# Grove_-_CO2_Temperature_Humidity_Sensor_.net
KiCad netlist of a schematic drawn in EAGLE
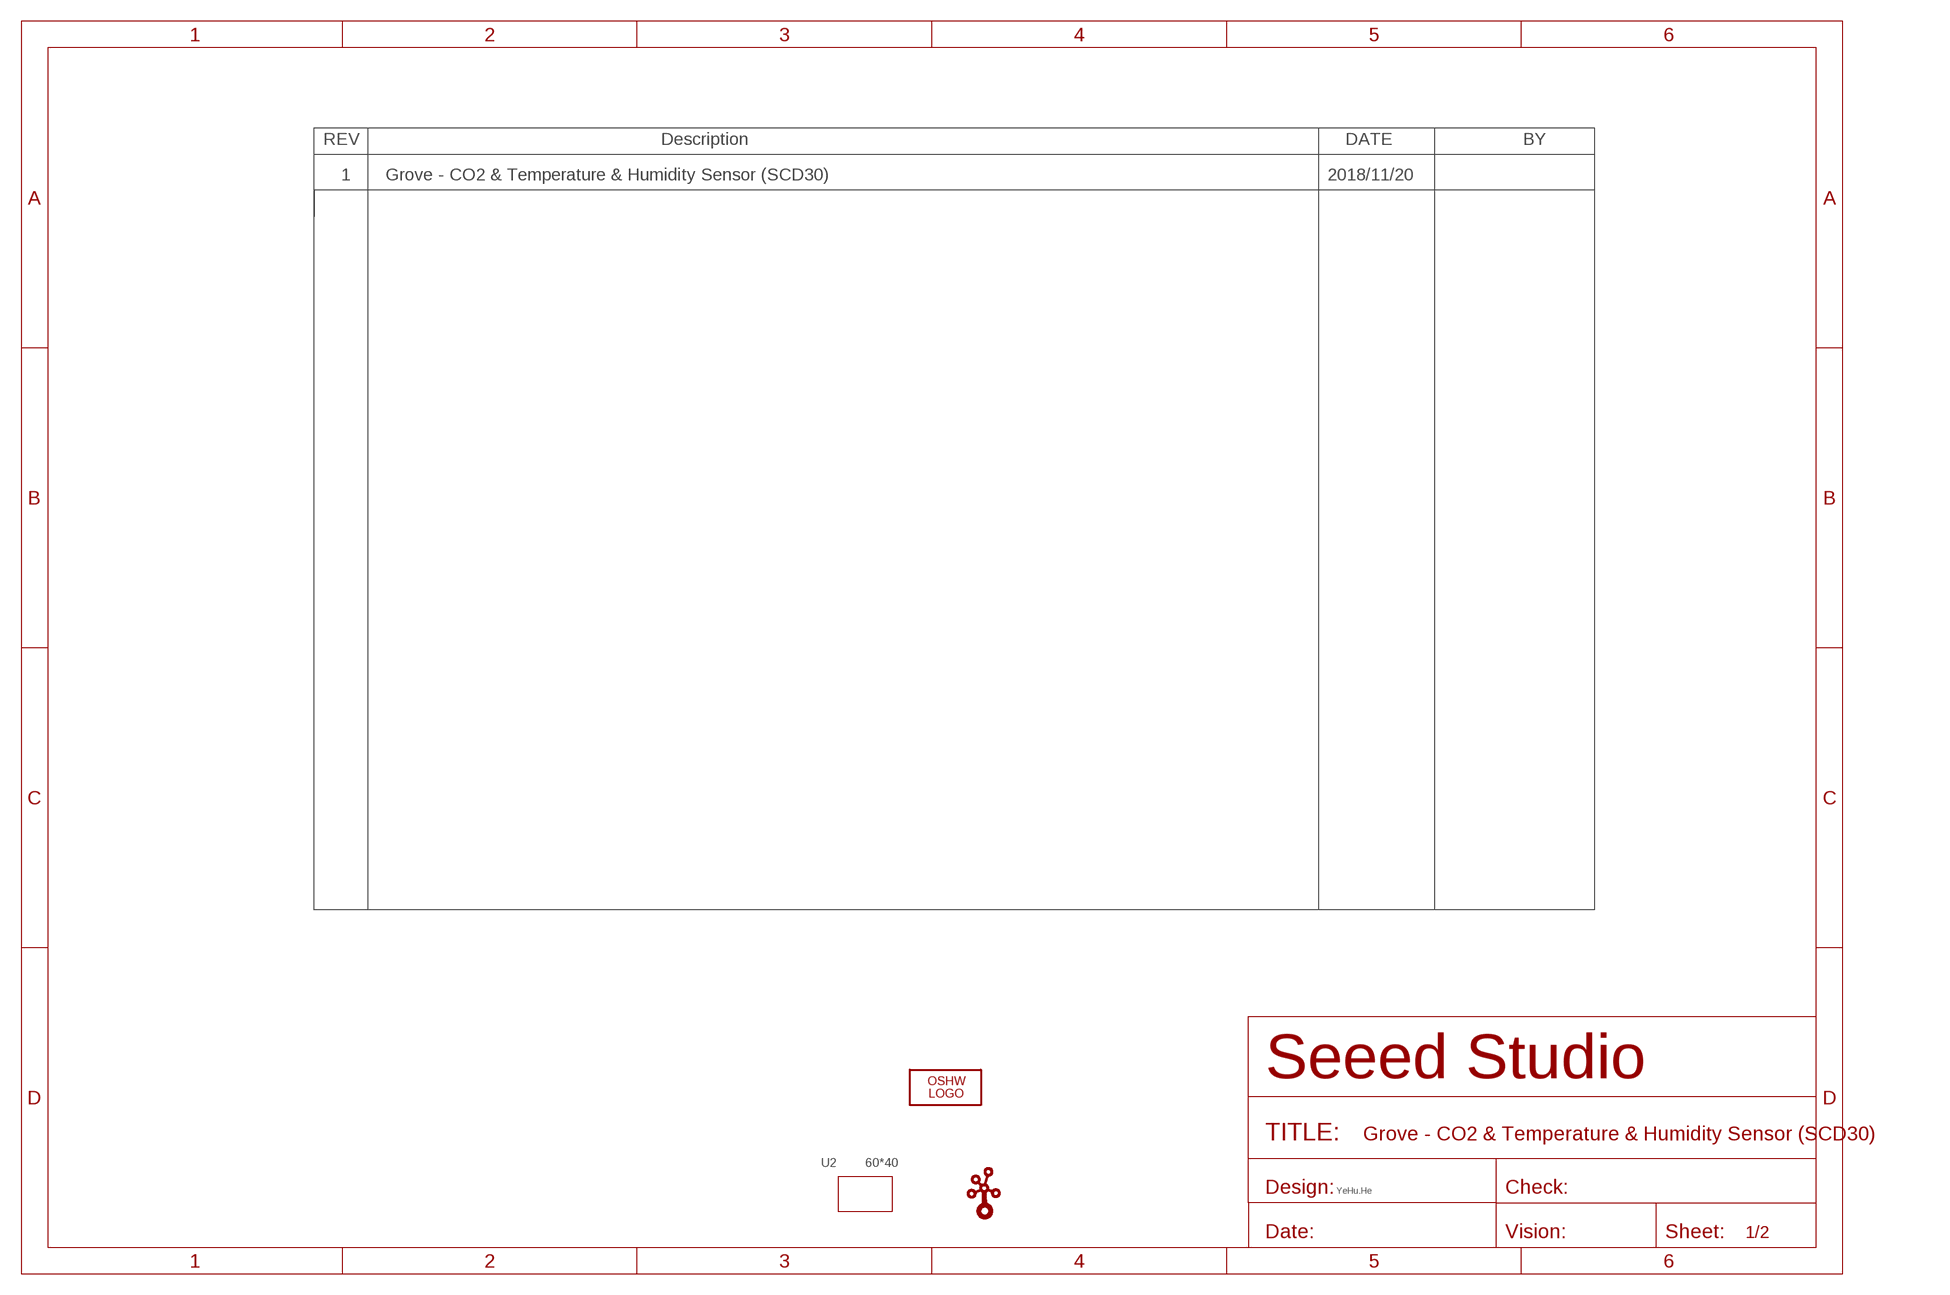
[diagram p0: schematic, sheet 1]
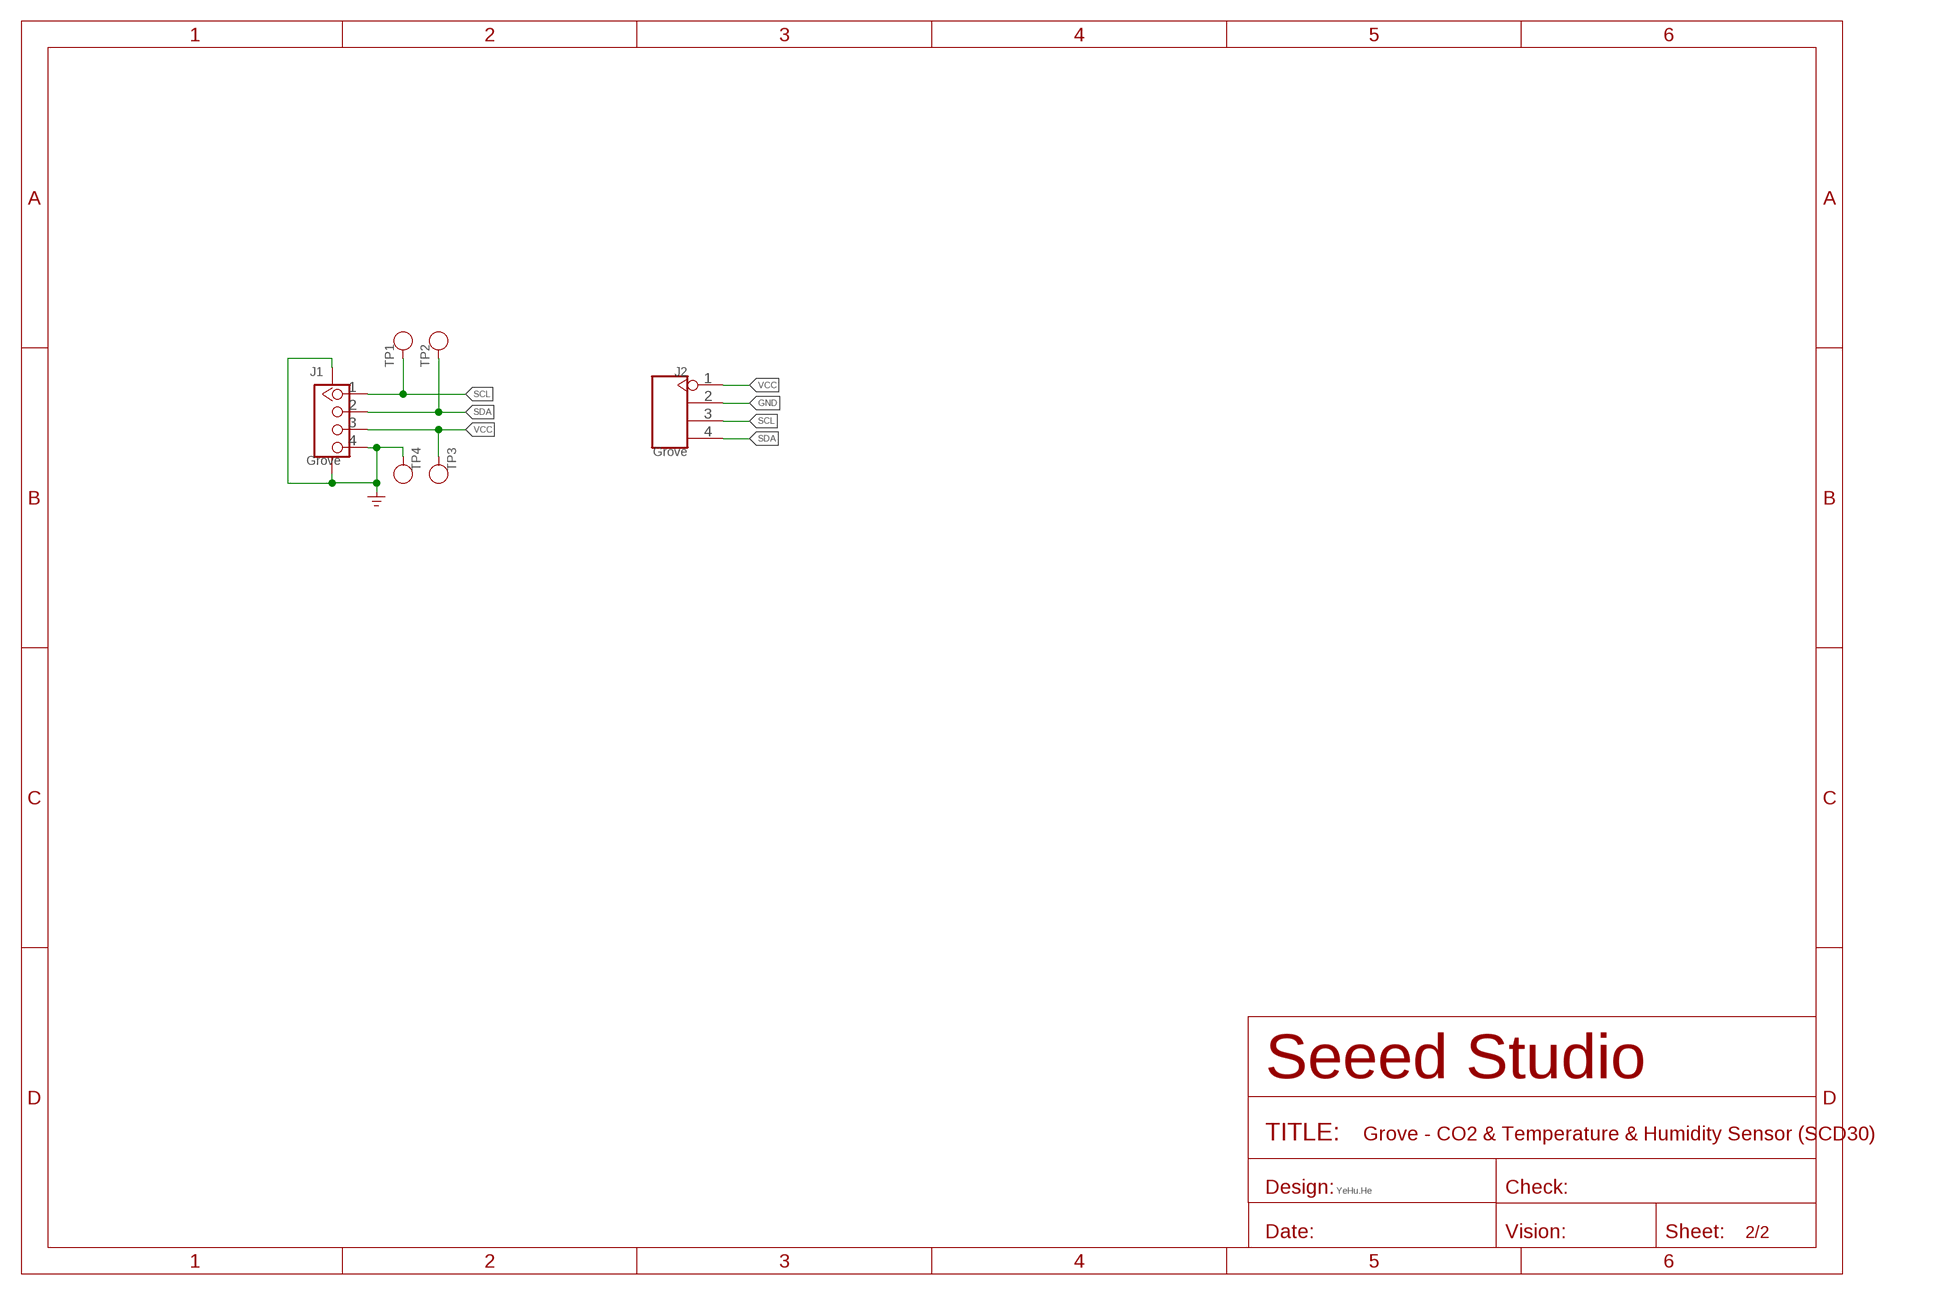
[diagram p1: schematic, sheet 2]

(export (version "E")
  (design (tool "Eeschema 10.0.6"))
  (components
    (comp (ref "J1")
      (value "Grove")
      (footprint "eagle-import:HW4-SMD-2.0-90D")
      (libsource (lib "eagle-import") (part "GROVE-CONNECTOR-SMD'90D'"))
    )
    (comp (ref "J2")
      (value "Grove")
      (footprint "eagle-import:H4-2.54")
      (libsource (lib "eagle-import") (part "HEADER-4P-65/35MIL"))
    )
    (comp (ref "TP1")
      (value "Test")
      (footprint "eagle-import:TP-D45MIL")
      (fields (field (name "PARTNO") "DNP"))
      (libsource (lib "eagle-import") (part "TEST-POINT'4545'"))
    )
    (comp (ref "TP2")
      (value "Test")
      (footprint "eagle-import:TP-D45MIL")
      (fields (field (name "PARTNO") "DNP"))
      (libsource (lib "eagle-import") (part "TEST-POINT'4545'"))
    )
    (comp (ref "TP3")
      (value "Test")
      (footprint "eagle-import:TP-D45MIL")
      (fields (field (name "PARTNO") "DNP"))
      (libsource (lib "eagle-import") (part "TEST-POINT'4545'"))
    )
    (comp (ref "TP4")
      (value "Test")
      (footprint "eagle-import:TP-D45MIL")
      (fields (field (name "PARTNO") "DNP"))
      (libsource (lib "eagle-import") (part "TEST-POINT'4545'"))
    )
    (comp (ref "LOGO1")
      (value "LOGO-OSHW-FILLX0200-NT")
      (footprint "eagle-import:OSHW_FILLX200_NOTEXT")
      (fields (field (name "PARTNO") "DNP"))
      (libsource (lib "eagle-import") (part "LOGO-OSHW-FILLX0200-NT"))
    )
    (comp (ref "U$4")
      (value "LOGO-GROVE")
      (footprint "eagle-import:GROVE-SILK-BIG")
      (fields (field (name "PARTNO") "DNP"))
      (libsource (lib "eagle-import") (part "LOGO-GROVE"))
    )
    (comp (ref "U2")
      (value "60*40")
      (footprint "eagle-import:GROVE-60X40MM")
      (libsource (lib "eagle-import") (part "GROVE-60X40MM"))
    )
  )
  (nets
    (net (code "1") (name "GND") (class "Default")
      (node (ref "J1") (pin "4") (pinfunction "4_4") (pintype "bidirectional"))
      (node (ref "J1") (pin "SS1") (pinfunction "SS1_SS1") (pintype "bidirectional"))
      (node (ref "J1") (pin "SS2") (pinfunction "SS2_SS2") (pintype "bidirectional"))
      (node (ref "J2") (pin "2") (pinfunction "P$2_2") (pintype "bidirectional"))
      (node (ref "TP4") (pin "T") (pinfunction "T_T") (pintype "bidirectional"))
    )
    (net (code "2") (name "SCL") (class "Default")
      (node (ref "J1") (pin "1") (pinfunction "1_1") (pintype "bidirectional"))
      (node (ref "J2") (pin "3") (pinfunction "P$3_3") (pintype "bidirectional"))
      (node (ref "TP1") (pin "T") (pinfunction "T_T") (pintype "bidirectional"))
    )
    (net (code "3") (name "SDA") (class "Default")
      (node (ref "J1") (pin "2") (pinfunction "2_2") (pintype "bidirectional"))
      (node (ref "J2") (pin "4") (pinfunction "P$4_4") (pintype "bidirectional"))
      (node (ref "TP2") (pin "T") (pinfunction "T_T") (pintype "bidirectional"))
    )
    (net (code "4") (name "VCC") (class "Default")
      (node (ref "J1") (pin "3") (pinfunction "3_3") (pintype "bidirectional"))
      (node (ref "J2") (pin "1") (pinfunction "P$1_1") (pintype "bidirectional"))
      (node (ref "TP3") (pin "T") (pinfunction "T_T") (pintype "bidirectional"))
    )
  )
)
